# shield.net
KiCad netlist of a schematic drawn in Altium Designer
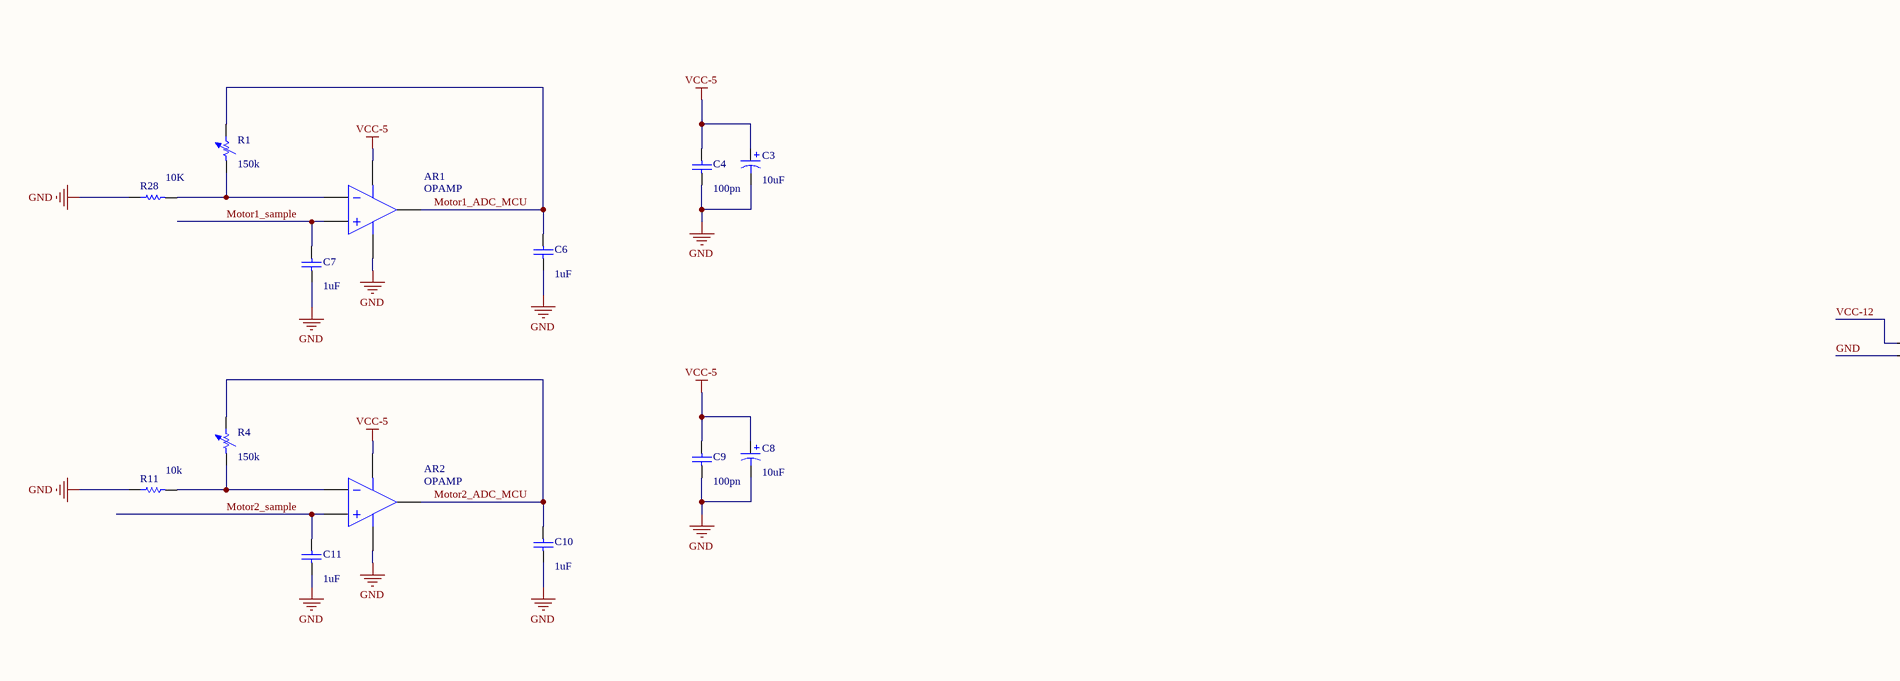
[diagram p0: shield.SchDoc, top left]
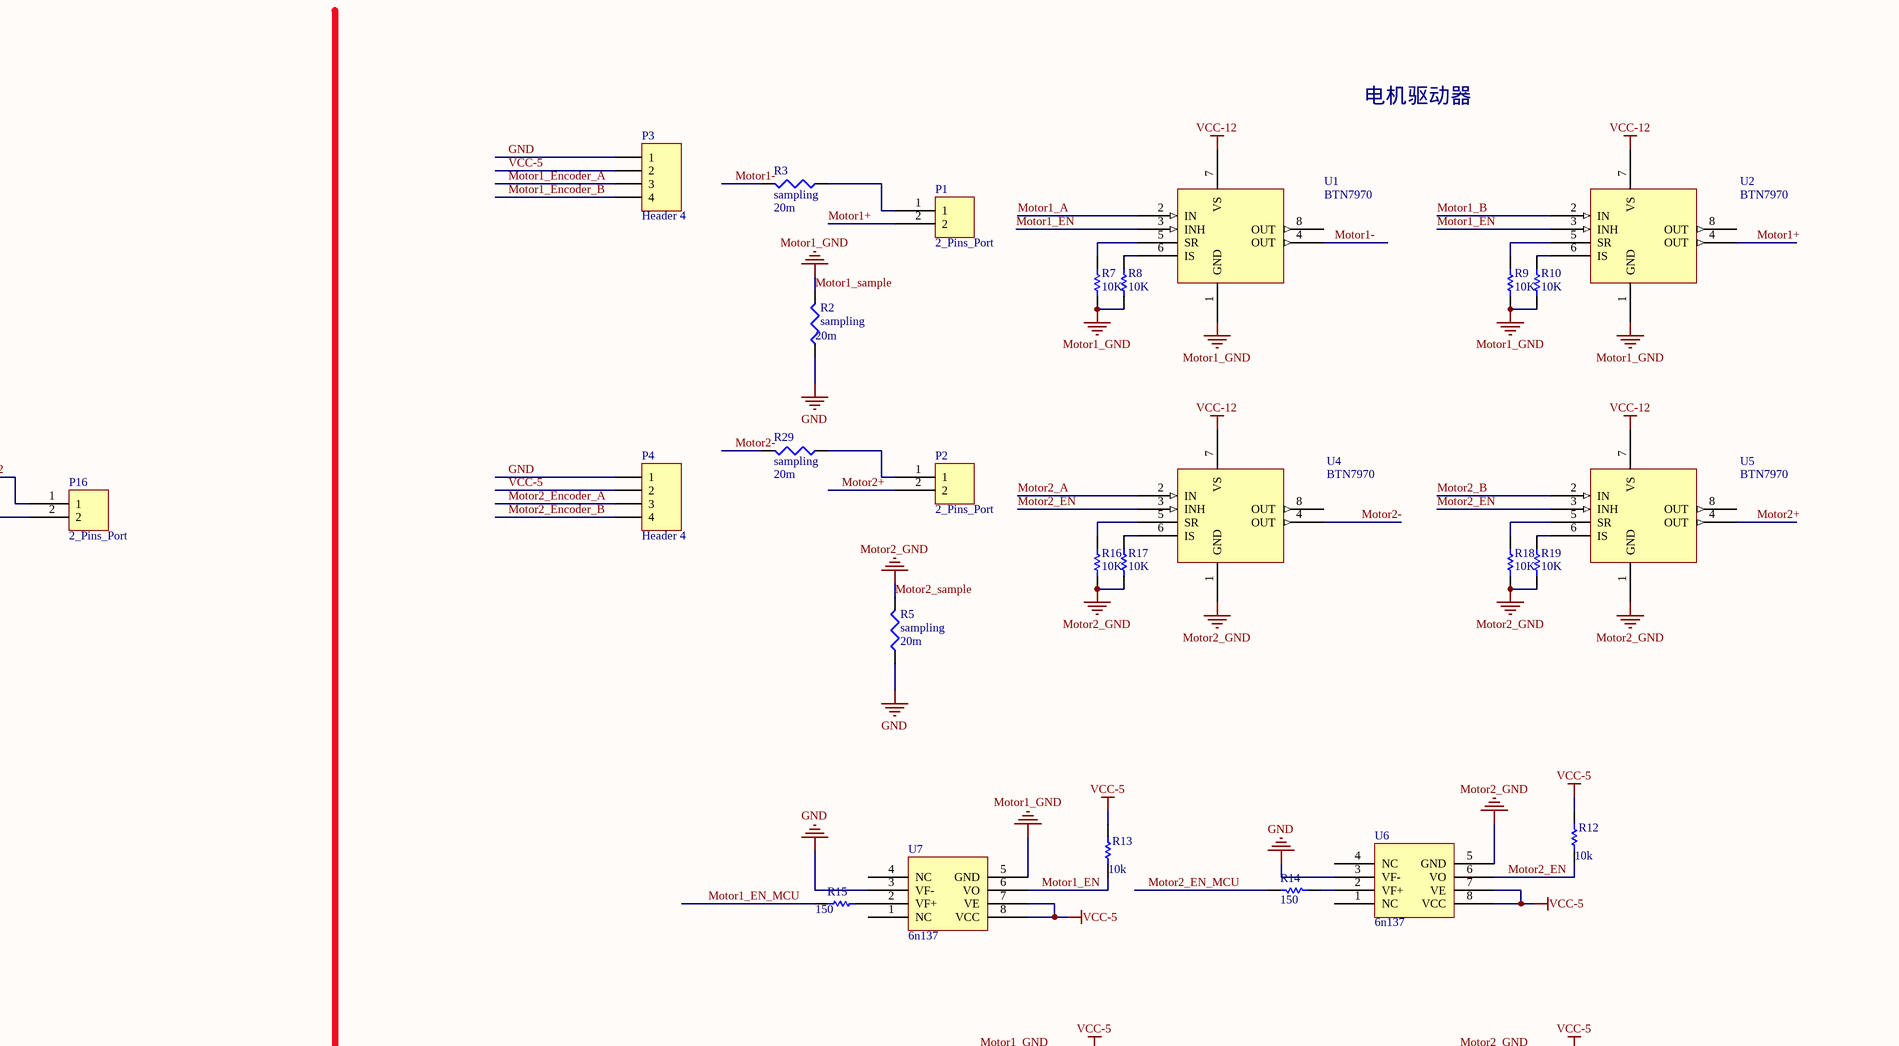
[diagram p1: shield.SchDoc, top right]
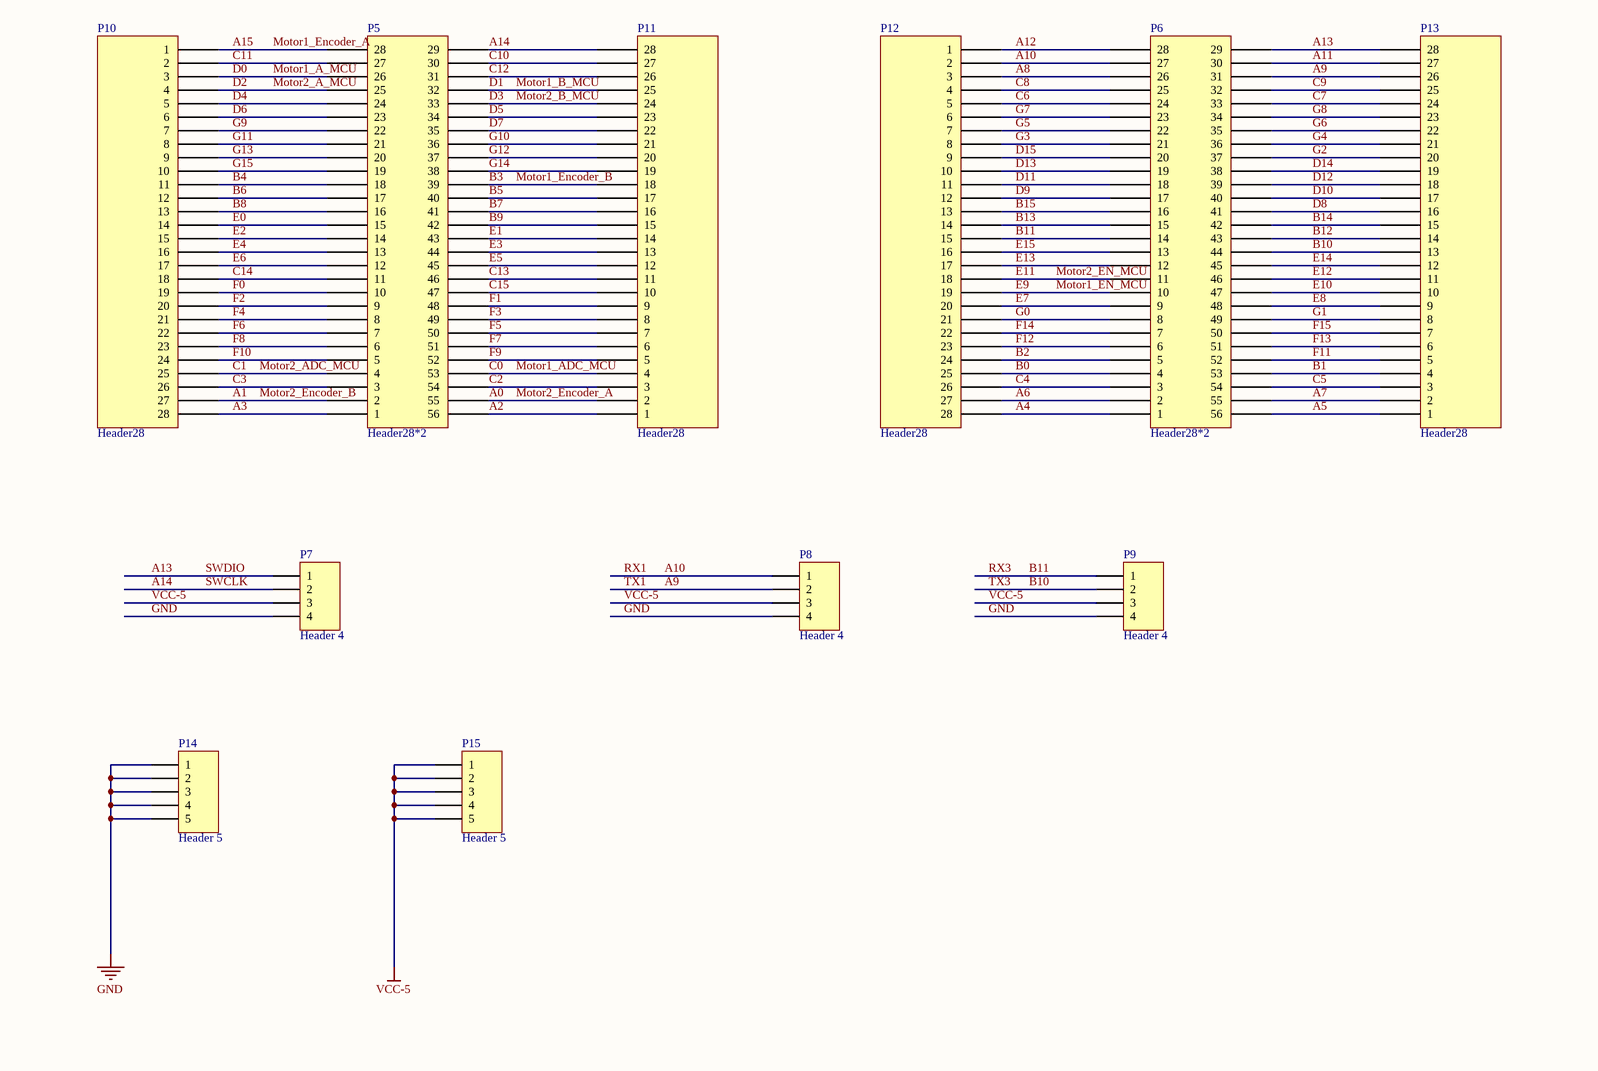
[diagram p2: shield.SchDoc, bottom left]
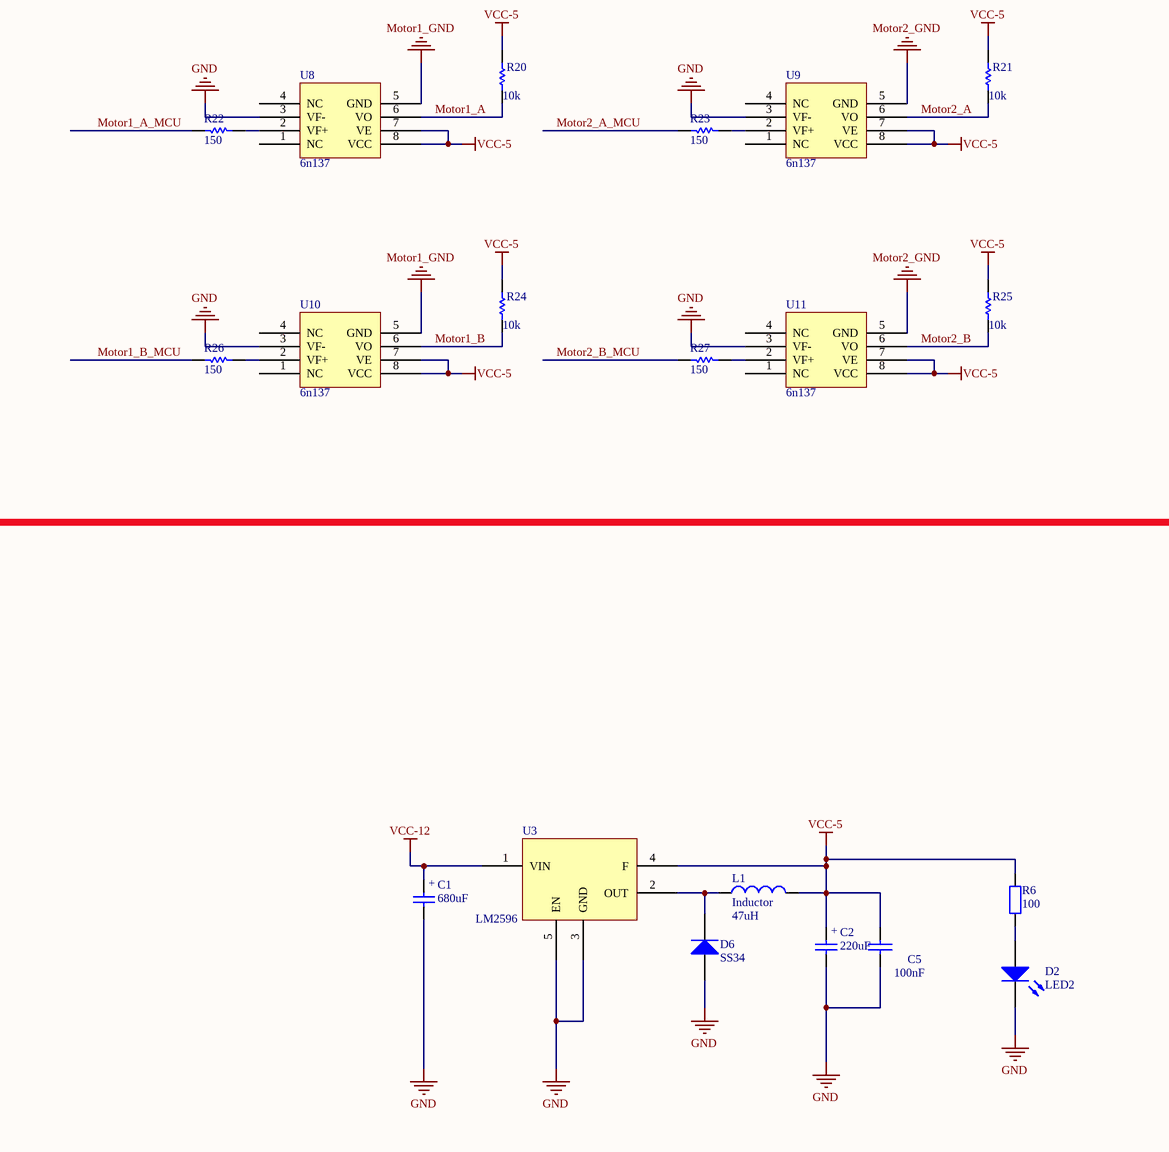
[diagram p3: shield.SchDoc, bottom right]

(export (version "E")
  (design (tool "Eeschema 10.0.6"))
  (components
    (comp (ref "AR1")
      (value "OPAMP")
      (footprint "LC-SO-8_3.9mm")
      (description "Operational Amplifier")
      (libsource (lib "SkyWorks2") (part "OPAMP"))
    )
    (comp (ref "AR2")
      (value "OPAMP")
      (footprint "LC-SO-8_3.9mm")
      (description "Operational Amplifier")
      (libsource (lib "SkyWorks2") (part "OPAMP"))
    )
    (comp (ref "C1")
      (value "680uF")
      (footprint "CAP-7343")
      (description "贴片极性电容")
      (fields (field (name "Comment") "Cap"))
      (libsource (lib "SkyWorks2") (part "Cap Pol S"))
    )
    (comp (ref "C2")
      (value "220uF")
      (footprint "CAP-7343")
      (description "贴片极性电容")
      (fields (field (name "Comment") "Cap"))
      (libsource (lib "SkyWorks2") (part "Cap Pol S"))
    )
    (comp (ref "C3")
      (value "10uF")
      (footprint "CAP-3528")
      (description "Polarized Capacitor (Radial)")
      (fields (field (name "Comment") "Cap Pol1") (field (name "PUBLISHER") "Altium Limited"))
      (libsource (lib "Miscellaneous Devices") (part "Cap Pol1"))
    )
    (comp (ref "C4")
      (value "100pn")
      (footprint "CAP-0603")
      (description "Capacitor")
      (fields (field (name "Comment") "Cap") (field (name "PUBLISHER") "Altium Limited"))
      (libsource (lib "Miscellaneous Devices") (part "Cap"))
    )
    (comp (ref "C5")
      (value "100nF")
      (footprint "CAP-0603")
      (description "贴片无极性电容")
      (fields (field (name "Comment") "cap smd"))
      (libsource (lib "SkyWorks2") (part "CAP"))
    )
    (comp (ref "C6")
      (value "1uF")
      (footprint "CAP-0603")
      (description "Capacitor")
      (fields (field (name "Comment") "Cap") (field (name "PUBLISHER") "Altium Limited"))
      (libsource (lib "Miscellaneous Devices") (part "Cap"))
    )
    (comp (ref "C7")
      (value "1uF")
      (footprint "CAP-0603")
      (description "Capacitor")
      (fields (field (name "Comment") "Cap") (field (name "PUBLISHER") "Altium Limited"))
      (libsource (lib "Miscellaneous Devices") (part "Cap"))
    )
    (comp (ref "C8")
      (value "10uF")
      (footprint "CAP-3528")
      (description "Polarized Capacitor (Radial)")
      (fields (field (name "Comment") "Cap Pol1") (field (name "PUBLISHER") "Altium Limited"))
      (libsource (lib "Miscellaneous Devices") (part "Cap Pol1"))
    )
    (comp (ref "C9")
      (value "100pn")
      (footprint "CAP-0603")
      (description "Capacitor")
      (fields (field (name "Comment") "Cap") (field (name "PUBLISHER") "Altium Limited"))
      (libsource (lib "Miscellaneous Devices") (part "Cap"))
    )
    (comp (ref "C10")
      (value "1uF")
      (footprint "CAP-0603")
      (description "Capacitor")
      (fields (field (name "Comment") "Cap") (field (name "PUBLISHER") "Altium Limited"))
      (libsource (lib "Miscellaneous Devices") (part "Cap"))
    )
    (comp (ref "C11")
      (value "1uF")
      (footprint "CAP-0603")
      (description "Capacitor")
      (fields (field (name "Comment") "Cap") (field (name "PUBLISHER") "Altium Limited"))
      (libsource (lib "Miscellaneous Devices") (part "Cap"))
    )
    (comp (ref "D2")
      (value "LED2")
      (footprint "D2012[0805]")
      (description "Typical RED, GREEN, YELLOW, AMBER GaAs LED")
      (fields (field (name "PUBLISHER") "Altium Limited"))
      (libsource (lib "SkyWorks2") (part "LED2"))
    )
    (comp (ref "D6")
      (value "SS34")
      (footprint "LC-SMB(DO-214AA)_S3")
      (description "3 Amp General Purpose Rectifier")
      (fields (field (name "PUBLISHER") "Altium Limited"))
      (libsource (lib "Miscellaneous Devices") (part "Diode 1N5400"))
    )
    (comp (ref "L1")
      (value "Inductor")
      (footprint "Inductor1207")
      (fields (field (name "ALTIUM_VALUE") "47uH") (field (name "PUBLISHER") "Altium Limited"))
      (libsource (lib "Miscellaneous Devices") (part "Inductor"))
    )
    (comp (ref "P1")
      (value "2_Pins_Port")
      (footprint "WJ2EDGV-5.08-2P")
      (libsource (lib "transhcan") (part "2_Pins_Port"))
    )
    (comp (ref "P2")
      (value "2_Pins_Port")
      (footprint "WJ2EDGV-5.08-2P")
      (libsource (lib "transhcan") (part "2_Pins_Port"))
    )
    (comp (ref "P3")
      (value "Header 4")
      (footprint "HDR1X4")
      (description "Header, 4-Pin")
      (fields (field (name "PUBLISHER") "Altium Limited"))
      (libsource (lib "Miscellaneous Connectors") (part "Header 4"))
    )
    (comp (ref "P4")
      (value "Header 4")
      (footprint "HDR1X4")
      (description "Header, 4-Pin")
      (fields (field (name "PUBLISHER") "Altium Limited"))
      (libsource (lib "Miscellaneous Connectors") (part "Header 4"))
    )
    (comp (ref "P5") (value "Header28*2") (footprint "HDR28*2") (libsource (lib "MLI") (part "header28*2")))
    (comp (ref "P6") (value "Header28*2") (footprint "HDR28*2") (libsource (lib "MLI") (part "header28*2")))
    (comp (ref "P7")
      (value "Header 4")
      (footprint "HDR1X4")
      (description "Header, 4-Pin")
      (fields (field (name "PUBLISHER") "Altium Limited"))
      (libsource (lib "Miscellaneous Connectors") (part "Header 4"))
    )
    (comp (ref "P8")
      (value "Header 4")
      (footprint "HDR1X4")
      (description "Header, 4-Pin")
      (fields (field (name "PUBLISHER") "Altium Limited"))
      (libsource (lib "Miscellaneous Connectors") (part "Header 4"))
    )
    (comp (ref "P9")
      (value "Header 4")
      (footprint "HDR1X4")
      (description "Header, 4-Pin")
      (fields (field (name "PUBLISHER") "Altium Limited"))
      (libsource (lib "Miscellaneous Connectors") (part "Header 4"))
    )
    (comp (ref "P10") (value "Header28") (footprint "HDR28") (libsource (lib "") (part "Header28_1")))
    (comp (ref "P11") (value "Header28") (footprint "HDR28") (libsource (lib "MLI") (part "Header28")))
    (comp (ref "P12") (value "Header28") (footprint "HDR28") (libsource (lib "") (part "Header28_1")))
    (comp (ref "P13") (value "Header28") (footprint "HDR28") (libsource (lib "MLI") (part "Header28")))
    (comp (ref "P14")
      (value "Header 5")
      (footprint "HDR1X5")
      (description "Header, 5-Pin")
      (fields (field (name "PUBLISHER") "Altium Limited"))
      (libsource (lib "Miscellaneous Connectors") (part "Header 5"))
    )
    (comp (ref "P15")
      (value "Header 5")
      (footprint "HDR1X5")
      (description "Header, 5-Pin")
      (fields (field (name "PUBLISHER") "Altium Limited"))
      (libsource (lib "Miscellaneous Connectors") (part "Header 5"))
    )
    (comp (ref "P16")
      (value "2_Pins_Port")
      (footprint "WJ2EDGV-5.08-2P")
      (libsource (lib "transhcan") (part "2_Pins_Port"))
    )
    (comp (ref "R1")
      (value "150k")
      (footprint "3266W")
      (description "Variable Resistor")
      (fields (field (name "Comment") "Res Adj1") (field (name "PUBLISHER") "Altium Limited"))
      (libsource (lib "Miscellaneous Devices") (part "Res Adj1"))
    )
    (comp (ref "R2")
      (value "sampling")
      (footprint "6332[2512]")
      (description "Resistor")
      (fields (field (name "ALTIUM_VALUE") "20m") (field (name "PUBLISHER") "Altium Limited"))
      (libsource (lib "Miscellaneous Devices") (part "Res3"))
    )
    (comp (ref "R3")
      (value "sampling")
      (footprint "6332[2512]")
      (description "Resistor")
      (fields (field (name "ALTIUM_VALUE") "20m") (field (name "PUBLISHER") "Altium Limited"))
      (libsource (lib "Miscellaneous Devices") (part "Res3"))
    )
    (comp (ref "R4")
      (value "150k")
      (footprint "3266W")
      (description "Variable Resistor")
      (fields (field (name "Comment") "Res Adj1") (field (name "PUBLISHER") "Altium Limited"))
      (libsource (lib "Miscellaneous Devices") (part "Res Adj1"))
    )
    (comp (ref "R5")
      (value "sampling")
      (footprint "6332[2512]")
      (description "Resistor")
      (fields (field (name "ALTIUM_VALUE") "20m") (field (name "PUBLISHER") "Altium Limited"))
      (libsource (lib "Miscellaneous Devices") (part "Res3"))
    )
    (comp (ref "R6")
      (value "100")
      (footprint "RES-0603")
      (fields (field (name "Comment") "RES1"))
      (libsource (lib "SkyWorks2") (part "RES1"))
    )
    (comp (ref "R7")
      (value "10K")
      (footprint "RES-0603")
      (description "Resistor")
      (libsource (lib "MCU") (part "res1"))
    )
    (comp (ref "R8")
      (value "10K")
      (footprint "RES-0603")
      (description "Resistor")
      (libsource (lib "MCU") (part "res1"))
    )
    (comp (ref "R9")
      (value "10K")
      (footprint "RES-0603")
      (description "Resistor")
      (libsource (lib "MCU") (part "res1"))
    )
    (comp (ref "R10")
      (value "10K")
      (footprint "RES-0603")
      (description "Resistor")
      (libsource (lib "MCU") (part "res1"))
    )
    (comp (ref "R11")
      (value "10k")
      (footprint "RES-0603")
      (description "Resistor")
      (fields (field (name "Comment") "Res1") (field (name "PUBLISHER") "Altium Limited"))
      (libsource (lib "Miscellaneous Devices") (part "Res1"))
    )
    (comp (ref "R12")
      (value "10k")
      (footprint "RES-0603")
      (description "Resistor")
      (fields (field (name "Comment") "Res1") (field (name "PUBLISHER") "Altium Limited"))
      (libsource (lib "Miscellaneous Devices") (part "Res1"))
    )
    (comp (ref "R13")
      (value "10k")
      (footprint "RES-0603")
      (description "Resistor")
      (fields (field (name "Comment") "Res1") (field (name "PUBLISHER") "Altium Limited"))
      (libsource (lib "Miscellaneous Devices") (part "Res1"))
    )
    (comp (ref "R14")
      (value "150")
      (footprint "RES-0603")
      (description "Resistor")
      (fields (field (name "Comment") "Res1") (field (name "PUBLISHER") "Altium Limited"))
      (libsource (lib "Miscellaneous Devices") (part "Res1"))
    )
    (comp (ref "R15")
      (value "150")
      (footprint "RES-0603")
      (description "Resistor")
      (fields (field (name "Comment") "Res1") (field (name "PUBLISHER") "Altium Limited"))
      (libsource (lib "Miscellaneous Devices") (part "Res1"))
    )
    (comp (ref "R16")
      (value "10K")
      (footprint "RES-0603")
      (description "Resistor")
      (libsource (lib "MCU") (part "res1"))
    )
    (comp (ref "R17")
      (value "10K")
      (footprint "RES-0603")
      (description "Resistor")
      (libsource (lib "MCU") (part "res1"))
    )
    (comp (ref "R18")
      (value "10K")
      (footprint "RES-0603")
      (description "Resistor")
      (libsource (lib "MCU") (part "res1"))
    )
    (comp (ref "R19")
      (value "10K")
      (footprint "RES-0603")
      (description "Resistor")
      (libsource (lib "MCU") (part "res1"))
    )
    (comp (ref "R20")
      (value "10k")
      (footprint "RES-0603")
      (description "Resistor")
      (fields (field (name "Comment") "Res1") (field (name "PUBLISHER") "Altium Limited"))
      (libsource (lib "Miscellaneous Devices") (part "Res1"))
    )
    (comp (ref "R21")
      (value "10k")
      (footprint "RES-0603")
      (description "Resistor")
      (fields (field (name "Comment") "Res1") (field (name "PUBLISHER") "Altium Limited"))
      (libsource (lib "Miscellaneous Devices") (part "Res1"))
    )
    (comp (ref "R22")
      (value "150")
      (footprint "RES-0603")
      (description "Resistor")
      (fields (field (name "Comment") "Res1") (field (name "PUBLISHER") "Altium Limited"))
      (libsource (lib "Miscellaneous Devices") (part "Res1"))
    )
    (comp (ref "R23")
      (value "150")
      (footprint "RES-0603")
      (description "Resistor")
      (fields (field (name "Comment") "Res1") (field (name "PUBLISHER") "Altium Limited"))
      (libsource (lib "Miscellaneous Devices") (part "Res1"))
    )
    (comp (ref "R24")
      (value "10k")
      (footprint "RES-0603")
      (description "Resistor")
      (fields (field (name "Comment") "Res1") (field (name "PUBLISHER") "Altium Limited"))
      (libsource (lib "Miscellaneous Devices") (part "Res1"))
    )
    (comp (ref "R25")
      (value "10k")
      (footprint "RES-0603")
      (description "Resistor")
      (fields (field (name "Comment") "Res1") (field (name "PUBLISHER") "Altium Limited"))
      (libsource (lib "Miscellaneous Devices") (part "Res1"))
    )
    (comp (ref "R26")
      (value "150")
      (footprint "RES-0603")
      (description "Resistor")
      (fields (field (name "Comment") "Res1") (field (name "PUBLISHER") "Altium Limited"))
      (libsource (lib "Miscellaneous Devices") (part "Res1"))
    )
    (comp (ref "R27")
      (value "150")
      (footprint "RES-0603")
      (description "Resistor")
      (fields (field (name "Comment") "Res1") (field (name "PUBLISHER") "Altium Limited"))
      (libsource (lib "Miscellaneous Devices") (part "Res1"))
    )
    (comp (ref "R28")
      (value "10K")
      (footprint "RES-0603")
      (description "Resistor")
      (fields (field (name "Comment") "Res1") (field (name "PUBLISHER") "Altium Limited"))
      (libsource (lib "Miscellaneous Devices") (part "Res1"))
    )
    (comp (ref "R29")
      (value "sampling")
      (footprint "6332[2512]")
      (description "Resistor")
      (fields (field (name "ALTIUM_VALUE") "20m") (field (name "PUBLISHER") "Altium Limited"))
      (libsource (lib "Miscellaneous Devices") (part "Res3"))
    )
    (comp (ref "U1") (value "BTN7970") (footprint "BTN7970") (libsource (lib "transhcan") (part "BTN7970")))
    (comp (ref "U2") (value "BTN7970") (footprint "BTN7970") (libsource (lib "transhcan") (part "BTN7970")))
    (comp (ref "U3") (value "LM2596") (footprint "LC-TO-263-5") (libsource (lib "MLI") (part "LM2596")))
    (comp (ref "U4") (value "BTN7970") (footprint "BTN7970") (libsource (lib "transhcan") (part "BTN7970")))
    (comp (ref "U5") (value "BTN7970") (footprint "BTN7970") (libsource (lib "transhcan") (part "BTN7970")))
    (comp (ref "U6") (value "6n137") (libsource (lib "MLI") (part "6n137")))
    (comp (ref "U7") (value "6n137") (libsource (lib "MLI") (part "6n137")))
    (comp (ref "U8") (value "6n137") (libsource (lib "MLI") (part "6n137")))
    (comp (ref "U9") (value "6n137") (libsource (lib "MLI") (part "6n137")))
    (comp (ref "U10") (value "6n137") (libsource (lib "MLI") (part "6n137")))
    (comp (ref "U11") (value "6n137") (libsource (lib "MLI") (part "6n137")))
  )
  (nets
    (net (code "1") (name "/A0") (class "Default")
      (node (ref "P11") (pin "2") (pinfunction "2_2") (pintype "passive"))
      (node (ref "P4") (pin "3") (pinfunction "3_3") (pintype "passive"))
      (node (ref "P5") (pin "55") (pinfunction "55_55") (pintype "passive"))
    )
    (net (code "2") (name "/A1") (class "Default")
      (node (ref "P10") (pin "27") (pinfunction "27_27") (pintype "passive"))
      (node (ref "P4") (pin "4") (pinfunction "4_4") (pintype "passive"))
      (node (ref "P5") (pin "2") (pinfunction "2_2") (pintype "passive"))
    )
    (net (code "3") (name "/A2") (class "Default")
      (node (ref "P11") (pin "1") (pinfunction "1_1") (pintype "passive"))
      (node (ref "P5") (pin "56") (pinfunction "56_56") (pintype "passive"))
    )
    (net (code "4") (name "/A3") (class "Default")
      (node (ref "P10") (pin "28") (pinfunction "28_28") (pintype "passive"))
      (node (ref "P5") (pin "1") (pinfunction "1_1") (pintype "passive"))
    )
    (net (code "5") (name "/A4") (class "Default")
      (node (ref "P12") (pin "28") (pinfunction "28_28") (pintype "passive"))
      (node (ref "P6") (pin "1") (pinfunction "1_1") (pintype "passive"))
    )
    (net (code "6") (name "/A5") (class "Default")
      (node (ref "P13") (pin "1") (pinfunction "1_1") (pintype "passive"))
      (node (ref "P6") (pin "56") (pinfunction "56_56") (pintype "passive"))
    )
    (net (code "7") (name "/A6") (class "Default")
      (node (ref "P12") (pin "27") (pinfunction "27_27") (pintype "passive"))
      (node (ref "P6") (pin "2") (pinfunction "2_2") (pintype "passive"))
    )
    (net (code "8") (name "/A7") (class "Default")
      (node (ref "P13") (pin "2") (pinfunction "2_2") (pintype "passive"))
      (node (ref "P6") (pin "55") (pinfunction "55_55") (pintype "passive"))
    )
    (net (code "9") (name "/A8") (class "Default")
      (node (ref "P12") (pin "3") (pinfunction "3_3") (pintype "passive"))
      (node (ref "P6") (pin "26") (pinfunction "26_26") (pintype "passive"))
    )
    (net (code "10") (name "/A9") (class "Default")
      (node (ref "P13") (pin "26") (pinfunction "26_26") (pintype "passive"))
      (node (ref "P6") (pin "31") (pinfunction "31_31") (pintype "passive"))
      (node (ref "P8") (pin "2") (pinfunction "2_2") (pintype "passive"))
    )
    (net (code "11") (name "/A10") (class "Default")
      (node (ref "P12") (pin "2") (pinfunction "2_2") (pintype "passive"))
      (node (ref "P6") (pin "27") (pinfunction "27_27") (pintype "passive"))
      (node (ref "P8") (pin "1") (pinfunction "1_1") (pintype "passive"))
    )
    (net (code "12") (name "/A11") (class "Default")
      (node (ref "P13") (pin "27") (pinfunction "27_27") (pintype "passive"))
      (node (ref "P6") (pin "30") (pinfunction "30_30") (pintype "passive"))
    )
    (net (code "13") (name "/A12") (class "Default")
      (node (ref "P12") (pin "1") (pinfunction "1_1") (pintype "passive"))
      (node (ref "P6") (pin "28") (pinfunction "28_28") (pintype "passive"))
    )
    (net (code "14") (name "/A13") (class "Default")
      (node (ref "P13") (pin "28") (pinfunction "28_28") (pintype "passive"))
      (node (ref "P6") (pin "29") (pinfunction "29_29") (pintype "passive"))
      (node (ref "P7") (pin "1") (pinfunction "1_1") (pintype "passive"))
    )
    (net (code "15") (name "/A14") (class "Default")
      (node (ref "P11") (pin "28") (pinfunction "28_28") (pintype "passive"))
      (node (ref "P5") (pin "29") (pinfunction "29_29") (pintype "passive"))
      (node (ref "P7") (pin "2") (pinfunction "2_2") (pintype "passive"))
    )
    (net (code "16") (name "/A15") (class "Default")
      (node (ref "P10") (pin "1") (pinfunction "1_1") (pintype "passive"))
      (node (ref "P3") (pin "3") (pinfunction "3_3") (pintype "passive"))
      (node (ref "P5") (pin "28") (pinfunction "28_28") (pintype "passive"))
    )
    (net (code "17") (name "/B0") (class "Default")
      (node (ref "P12") (pin "25") (pinfunction "25_25") (pintype "passive"))
      (node (ref "P6") (pin "4") (pinfunction "4_4") (pintype "passive"))
    )
    (net (code "18") (name "/B1") (class "Default")
      (node (ref "P13") (pin "4") (pinfunction "4_4") (pintype "passive"))
      (node (ref "P6") (pin "53") (pinfunction "53_53") (pintype "passive"))
    )
    (net (code "19") (name "/B2") (class "Default")
      (node (ref "P12") (pin "24") (pinfunction "24_24") (pintype "passive"))
      (node (ref "P6") (pin "5") (pinfunction "5_5") (pintype "passive"))
    )
    (net (code "20") (name "/B3") (class "Default")
      (node (ref "P11") (pin "18") (pinfunction "18_18") (pintype "passive"))
      (node (ref "P3") (pin "4") (pinfunction "4_4") (pintype "passive"))
      (node (ref "P5") (pin "39") (pinfunction "39_39") (pintype "passive"))
    )
    (net (code "21") (name "/B4") (class "Default")
      (node (ref "P10") (pin "11") (pinfunction "11_11") (pintype "passive"))
      (node (ref "P5") (pin "18") (pinfunction "18_18") (pintype "passive"))
    )
    (net (code "22") (name "/B5") (class "Default")
      (node (ref "P11") (pin "17") (pinfunction "17_17") (pintype "passive"))
      (node (ref "P5") (pin "40") (pinfunction "40_40") (pintype "passive"))
    )
    (net (code "23") (name "/B6") (class "Default")
      (node (ref "P10") (pin "12") (pinfunction "12_12") (pintype "passive"))
      (node (ref "P5") (pin "17") (pinfunction "17_17") (pintype "passive"))
    )
    (net (code "24") (name "/B7") (class "Default")
      (node (ref "P11") (pin "16") (pinfunction "16_16") (pintype "passive"))
      (node (ref "P5") (pin "41") (pinfunction "41_41") (pintype "passive"))
    )
    (net (code "25") (name "/B8") (class "Default")
      (node (ref "P10") (pin "13") (pinfunction "13_13") (pintype "passive"))
      (node (ref "P5") (pin "16") (pinfunction "16_16") (pintype "passive"))
    )
    (net (code "26") (name "/B9") (class "Default")
      (node (ref "P11") (pin "15") (pinfunction "15_15") (pintype "passive"))
      (node (ref "P5") (pin "42") (pinfunction "42_42") (pintype "passive"))
    )
    (net (code "27") (name "/B10") (class "Default")
      (node (ref "P13") (pin "13") (pinfunction "13_13") (pintype "passive"))
      (node (ref "P6") (pin "44") (pinfunction "44_44") (pintype "passive"))
      (node (ref "P9") (pin "2") (pinfunction "2_2") (pintype "passive"))
    )
    (net (code "28") (name "/B11") (class "Default")
      (node (ref "P12") (pin "15") (pinfunction "15_15") (pintype "passive"))
      (node (ref "P6") (pin "14") (pinfunction "14_14") (pintype "passive"))
      (node (ref "P9") (pin "1") (pinfunction "1_1") (pintype "passive"))
    )
    (net (code "29") (name "/B12") (class "Default")
      (node (ref "P13") (pin "14") (pinfunction "14_14") (pintype "passive"))
      (node (ref "P6") (pin "43") (pinfunction "43_43") (pintype "passive"))
    )
    (net (code "30") (name "/B13") (class "Default")
      (node (ref "P12") (pin "14") (pinfunction "14_14") (pintype "passive"))
      (node (ref "P6") (pin "15") (pinfunction "15_15") (pintype "passive"))
    )
    (net (code "31") (name "/B14") (class "Default")
      (node (ref "P13") (pin "15") (pinfunction "15_15") (pintype "passive"))
      (node (ref "P6") (pin "42") (pinfunction "42_42") (pintype "passive"))
    )
    (net (code "32") (name "/B15") (class "Default")
      (node (ref "P12") (pin "13") (pinfunction "13_13") (pintype "passive"))
      (node (ref "P6") (pin "16") (pinfunction "16_16") (pintype "passive"))
    )
    (net (code "33") (name "/C0") (class "Default")
      (node (ref "AR1") (pin "3") (pinfunction "OUT_3") (pintype "passive"))
      (node (ref "C6") (pin "2") (pinfunction "2_2") (pintype "passive"))
      (node (ref "P11") (pin "4") (pinfunction "4_4") (pintype "passive"))
      (node (ref "P5") (pin "53") (pinfunction "53_53") (pintype "passive"))
      (node (ref "R1") (pin "2") (pinfunction "2_2") (pintype "passive"))
    )
    (net (code "34") (name "/C1") (class "Default")
      (node (ref "AR2") (pin "3") (pinfunction "OUT_3") (pintype "passive"))
      (node (ref "C10") (pin "2") (pinfunction "2_2") (pintype "passive"))
      (node (ref "P10") (pin "25") (pinfunction "25_25") (pintype "passive"))
      (node (ref "P5") (pin "4") (pinfunction "4_4") (pintype "passive"))
      (node (ref "R4") (pin "2") (pinfunction "2_2") (pintype "passive"))
    )
    (net (code "35") (name "/C2") (class "Default")
      (node (ref "P11") (pin "3") (pinfunction "3_3") (pintype "passive"))
      (node (ref "P5") (pin "54") (pinfunction "54_54") (pintype "passive"))
    )
    (net (code "36") (name "/C3") (class "Default")
      (node (ref "P10") (pin "26") (pinfunction "26_26") (pintype "passive"))
      (node (ref "P5") (pin "3") (pinfunction "3_3") (pintype "passive"))
    )
    (net (code "37") (name "/C4") (class "Default")
      (node (ref "P12") (pin "26") (pinfunction "26_26") (pintype "passive"))
      (node (ref "P6") (pin "3") (pinfunction "3_3") (pintype "passive"))
    )
    (net (code "38") (name "/C5") (class "Default")
      (node (ref "P13") (pin "3") (pinfunction "3_3") (pintype "passive"))
      (node (ref "P6") (pin "54") (pinfunction "54_54") (pintype "passive"))
    )
    (net (code "39") (name "/C6") (class "Default")
      (node (ref "P12") (pin "5") (pinfunction "5_5") (pintype "passive"))
      (node (ref "P6") (pin "24") (pinfunction "24_24") (pintype "passive"))
    )
    (net (code "40") (name "/C7") (class "Default")
      (node (ref "P13") (pin "24") (pinfunction "24_24") (pintype "passive"))
      (node (ref "P6") (pin "33") (pinfunction "33_33") (pintype "passive"))
    )
    (net (code "41") (name "/C8") (class "Default")
      (node (ref "P12") (pin "4") (pinfunction "4_4") (pintype "passive"))
      (node (ref "P6") (pin "25") (pinfunction "25_25") (pintype "passive"))
    )
    (net (code "42") (name "/C9") (class "Default")
      (node (ref "P13") (pin "25") (pinfunction "25_25") (pintype "passive"))
      (node (ref "P6") (pin "32") (pinfunction "32_32") (pintype "passive"))
    )
    (net (code "43") (name "/C10") (class "Default")
      (node (ref "P11") (pin "27") (pinfunction "27_27") (pintype "passive"))
      (node (ref "P5") (pin "30") (pinfunction "30_30") (pintype "passive"))
    )
    (net (code "44") (name "/C11") (class "Default")
      (node (ref "P10") (pin "2") (pinfunction "2_2") (pintype "passive"))
      (node (ref "P5") (pin "27") (pinfunction "27_27") (pintype "passive"))
    )
    (net (code "45") (name "/C12") (class "Default")
      (node (ref "P11") (pin "26") (pinfunction "26_26") (pintype "passive"))
      (node (ref "P5") (pin "31") (pinfunction "31_31") (pintype "passive"))
    )
    (net (code "46") (name "/C13") (class "Default")
      (node (ref "P11") (pin "11") (pinfunction "11_11") (pintype "passive"))
      (node (ref "P5") (pin "46") (pinfunction "46_46") (pintype "passive"))
    )
    (net (code "47") (name "/C14") (class "Default")
      (node (ref "P10") (pin "18") (pinfunction "18_18") (pintype "passive"))
      (node (ref "P5") (pin "11") (pinfunction "11_11") (pintype "passive"))
    )
    (net (code "48") (name "/C15") (class "Default")
      (node (ref "P11") (pin "10") (pinfunction "10_10") (pintype "passive"))
      (node (ref "P5") (pin "47") (pinfunction "47_47") (pintype "passive"))
    )
    (net (code "49") (name "/D0") (class "Default")
      (node (ref "P10") (pin "3") (pinfunction "3_3") (pintype "passive"))
      (node (ref "P5") (pin "26") (pinfunction "26_26") (pintype "passive"))
      (node (ref "R22") (pin "2") (pinfunction "2_2") (pintype "passive"))
    )
    (net (code "50") (name "/D1") (class "Default")
      (node (ref "P11") (pin "25") (pinfunction "25_25") (pintype "passive"))
      (node (ref "P5") (pin "32") (pinfunction "32_32") (pintype "passive"))
      (node (ref "R26") (pin "2") (pinfunction "2_2") (pintype "passive"))
    )
    (net (code "51") (name "/D2") (class "Default")
      (node (ref "P10") (pin "4") (pinfunction "4_4") (pintype "passive"))
      (node (ref "P5") (pin "25") (pinfunction "25_25") (pintype "passive"))
      (node (ref "R23") (pin "2") (pinfunction "2_2") (pintype "passive"))
    )
    (net (code "52") (name "/D3") (class "Default")
      (node (ref "P11") (pin "24") (pinfunction "24_24") (pintype "passive"))
      (node (ref "P5") (pin "33") (pinfunction "33_33") (pintype "passive"))
      (node (ref "R27") (pin "2") (pinfunction "2_2") (pintype "passive"))
    )
    (net (code "53") (name "/D4") (class "Default")
      (node (ref "P10") (pin "5") (pinfunction "5_5") (pintype "passive"))
      (node (ref "P5") (pin "24") (pinfunction "24_24") (pintype "passive"))
    )
    (net (code "54") (name "/D5") (class "Default")
      (node (ref "P11") (pin "23") (pinfunction "23_23") (pintype "passive"))
      (node (ref "P5") (pin "34") (pinfunction "34_34") (pintype "passive"))
    )
    (net (code "55") (name "/D6") (class "Default")
      (node (ref "P10") (pin "6") (pinfunction "6_6") (pintype "passive"))
      (node (ref "P5") (pin "23") (pinfunction "23_23") (pintype "passive"))
    )
    (net (code "56") (name "/D7") (class "Default")
      (node (ref "P11") (pin "22") (pinfunction "22_22") (pintype "passive"))
      (node (ref "P5") (pin "35") (pinfunction "35_35") (pintype "passive"))
    )
    (net (code "57") (name "/D8") (class "Default")
      (node (ref "P13") (pin "16") (pinfunction "16_16") (pintype "passive"))
      (node (ref "P6") (pin "41") (pinfunction "41_41") (pintype "passive"))
    )
    (net (code "58") (name "/D9") (class "Default")
      (node (ref "P12") (pin "12") (pinfunction "12_12") (pintype "passive"))
      (node (ref "P6") (pin "17") (pinfunction "17_17") (pintype "passive"))
    )
    (net (code "59") (name "/D10") (class "Default")
      (node (ref "P13") (pin "17") (pinfunction "17_17") (pintype "passive"))
      (node (ref "P6") (pin "40") (pinfunction "40_40") (pintype "passive"))
    )
    (net (code "60") (name "/D11") (class "Default")
      (node (ref "P12") (pin "11") (pinfunction "11_11") (pintype "passive"))
      (node (ref "P6") (pin "18") (pinfunction "18_18") (pintype "passive"))
    )
    (net (code "61") (name "/D12") (class "Default")
      (node (ref "P13") (pin "18") (pinfunction "18_18") (pintype "passive"))
      (node (ref "P6") (pin "39") (pinfunction "39_39") (pintype "passive"))
    )
    (net (code "62") (name "/D13") (class "Default")
      (node (ref "P12") (pin "10") (pinfunction "10_10") (pintype "passive"))
      (node (ref "P6") (pin "19") (pinfunction "19_19") (pintype "passive"))
    )
    (net (code "63") (name "/D14") (class "Default")
      (node (ref "P13") (pin "19") (pinfunction "19_19") (pintype "passive"))
      (node (ref "P6") (pin "38") (pinfunction "38_38") (pintype "passive"))
    )
    (net (code "64") (name "/D15") (class "Default")
      (node (ref "P12") (pin "9") (pinfunction "9_9") (pintype "passive"))
      (node (ref "P6") (pin "20") (pinfunction "20_20") (pintype "passive"))
    )
    (net (code "65") (name "/E0") (class "Default")
      (node (ref "P10") (pin "14") (pinfunction "14_14") (pintype "passive"))
      (node (ref "P5") (pin "15") (pinfunction "15_15") (pintype "passive"))
    )
    (net (code "66") (name "/E1") (class "Default")
      (node (ref "P11") (pin "14") (pinfunction "14_14") (pintype "passive"))
      (node (ref "P5") (pin "43") (pinfunction "43_43") (pintype "passive"))
    )
    (net (code "67") (name "/E2") (class "Default")
      (node (ref "P10") (pin "15") (pinfunction "15_15") (pintype "passive"))
      (node (ref "P5") (pin "14") (pinfunction "14_14") (pintype "passive"))
    )
    (net (code "68") (name "/E3") (class "Default")
      (node (ref "P11") (pin "13") (pinfunction "13_13") (pintype "passive"))
      (node (ref "P5") (pin "44") (pinfunction "44_44") (pintype "passive"))
    )
    (net (code "69") (name "/E4") (class "Default")
      (node (ref "P10") (pin "16") (pinfunction "16_16") (pintype "passive"))
      (node (ref "P5") (pin "13") (pinfunction "13_13") (pintype "passive"))
    )
    (net (code "70") (name "/E5") (class "Default")
      (node (ref "P11") (pin "12") (pinfunction "12_12") (pintype "passive"))
      (node (ref "P5") (pin "45") (pinfunction "45_45") (pintype "passive"))
    )
    (net (code "71") (name "/E6") (class "Default")
      (node (ref "P10") (pin "17") (pinfunction "17_17") (pintype "passive"))
      (node (ref "P5") (pin "12") (pinfunction "12_12") (pintype "passive"))
    )
    (net (code "72") (name "/E7") (class "Default")
      (node (ref "P12") (pin "20") (pinfunction "20_20") (pintype "passive"))
      (node (ref "P6") (pin "9") (pinfunction "9_9") (pintype "passive"))
    )
    (net (code "73") (name "/E8") (class "Default")
      (node (ref "P13") (pin "9") (pinfunction "9_9") (pintype "passive"))
      (node (ref "P6") (pin "48") (pinfunction "48_48") (pintype "passive"))
    )
    (net (code "74") (name "/E9") (class "Default")
      (node (ref "P12") (pin "19") (pinfunction "19_19") (pintype "passive"))
      (node (ref "P6") (pin "10") (pinfunction "10_10") (pintype "passive"))
      (node (ref "R15") (pin "2") (pinfunction "2_2") (pintype "passive"))
    )
    (net (code "75") (name "/E10") (class "Default")
      (node (ref "P13") (pin "10") (pinfunction "10_10") (pintype "passive"))
      (node (ref "P6") (pin "47") (pinfunction "47_47") (pintype "passive"))
    )
    (net (code "76") (name "/E11") (class "Default")
      (node (ref "P12") (pin "18") (pinfunction "18_18") (pintype "passive"))
      (node (ref "P6") (pin "11") (pinfunction "11_11") (pintype "passive"))
      (node (ref "R14") (pin "2") (pinfunction "2_2") (pintype "passive"))
    )
    (net (code "77") (name "/E12") (class "Default")
      (node (ref "P13") (pin "11") (pinfunction "11_11") (pintype "passive"))
      (node (ref "P6") (pin "46") (pinfunction "46_46") (pintype "passive"))
    )
    (net (code "78") (name "/E13") (class "Default")
      (node (ref "P12") (pin "17") (pinfunction "17_17") (pintype "passive"))
      (node (ref "P6") (pin "12") (pinfunction "12_12") (pintype "passive"))
    )
    (net (code "79") (name "/E14") (class "Default")
      (node (ref "P13") (pin "12") (pinfunction "12_12") (pintype "passive"))
      (node (ref "P6") (pin "45") (pinfunction "45_45") (pintype "passive"))
    )
    (net (code "80") (name "/E15") (class "Default")
      (node (ref "P12") (pin "16") (pinfunction "16_16") (pintype "passive"))
      (node (ref "P6") (pin "13") (pinfunction "13_13") (pintype "passive"))
    )
    (net (code "81") (name "/F0") (class "Default")
      (node (ref "P10") (pin "19") (pinfunction "19_19") (pintype "passive"))
      (node (ref "P5") (pin "10") (pinfunction "10_10") (pintype "passive"))
    )
    (net (code "82") (name "/F1") (class "Default")
      (node (ref "P11") (pin "9") (pinfunction "9_9") (pintype "passive"))
      (node (ref "P5") (pin "48") (pinfunction "48_48") (pintype "passive"))
    )
    (net (code "83") (name "/F2") (class "Default")
      (node (ref "P10") (pin "20") (pinfunction "20_20") (pintype "passive"))
      (node (ref "P5") (pin "9") (pinfunction "9_9") (pintype "passive"))
    )
    (net (code "84") (name "/F3") (class "Default")
      (node (ref "P11") (pin "8") (pinfunction "8_8") (pintype "passive"))
      (node (ref "P5") (pin "49") (pinfunction "49_49") (pintype "passive"))
    )
    (net (code "85") (name "/F4") (class "Default")
      (node (ref "P10") (pin "21") (pinfunction "21_21") (pintype "passive"))
      (node (ref "P5") (pin "8") (pinfunction "8_8") (pintype "passive"))
    )
    (net (code "86") (name "/F5") (class "Default")
      (node (ref "P11") (pin "7") (pinfunction "7_7") (pintype "passive"))
      (node (ref "P5") (pin "50") (pinfunction "50_50") (pintype "passive"))
    )
    (net (code "87") (name "/F6") (class "Default")
      (node (ref "P10") (pin "22") (pinfunction "22_22") (pintype "passive"))
      (node (ref "P5") (pin "7") (pinfunction "7_7") (pintype "passive"))
    )
    (net (code "88") (name "/F7") (class "Default")
      (node (ref "P11") (pin "6") (pinfunction "6_6") (pintype "passive"))
      (node (ref "P5") (pin "51") (pinfunction "51_51") (pintype "passive"))
    )
    (net (code "89") (name "/F8") (class "Default")
      (node (ref "P10") (pin "23") (pinfunction "23_23") (pintype "passive"))
      (node (ref "P5") (pin "6") (pinfunction "6_6") (pintype "passive"))
    )
    (net (code "90") (name "/F9") (class "Default")
      (node (ref "P11") (pin "5") (pinfunction "5_5") (pintype "passive"))
      (node (ref "P5") (pin "52") (pinfunction "52_52") (pintype "passive"))
    )
    (net (code "91") (name "/F10") (class "Default")
      (node (ref "P10") (pin "24") (pinfunction "24_24") (pintype "passive"))
      (node (ref "P5") (pin "5") (pinfunction "5_5") (pintype "passive"))
    )
    (net (code "92") (name "/F11") (class "Default")
      (node (ref "P13") (pin "5") (pinfunction "5_5") (pintype "passive"))
      (node (ref "P6") (pin "52") (pinfunction "52_52") (pintype "passive"))
    )
    (net (code "93") (name "/F12") (class "Default")
      (node (ref "P12") (pin "23") (pinfunction "23_23") (pintype "passive"))
      (node (ref "P6") (pin "6") (pinfunction "6_6") (pintype "passive"))
    )
    (net (code "94") (name "/F13") (class "Default")
      (node (ref "P13") (pin "6") (pinfunction "6_6") (pintype "passive"))
      (node (ref "P6") (pin "51") (pinfunction "51_51") (pintype "passive"))
    )
    (net (code "95") (name "/F14") (class "Default")
      (node (ref "P12") (pin "22") (pinfunction "22_22") (pintype "passive"))
      (node (ref "P6") (pin "7") (pinfunction "7_7") (pintype "passive"))
    )
    (net (code "96") (name "/F15") (class "Default")
      (node (ref "P13") (pin "7") (pinfunction "7_7") (pintype "passive"))
      (node (ref "P6") (pin "50") (pinfunction "50_50") (pintype "passive"))
    )
    (net (code "97") (name "/G0") (class "Default")
      (node (ref "P12") (pin "21") (pinfunction "21_21") (pintype "passive"))
      (node (ref "P6") (pin "8") (pinfunction "8_8") (pintype "passive"))
    )
    (net (code "98") (name "/G1") (class "Default")
      (node (ref "P13") (pin "8") (pinfunction "8_8") (pintype "passive"))
      (node (ref "P6") (pin "49") (pinfunction "49_49") (pintype "passive"))
    )
    (net (code "99") (name "/G2") (class "Default")
      (node (ref "P13") (pin "20") (pinfunction "20_20") (pintype "passive"))
      (node (ref "P6") (pin "37") (pinfunction "37_37") (pintype "passive"))
    )
    (net (code "100") (name "/G3") (class "Default")
      (node (ref "P12") (pin "8") (pinfunction "8_8") (pintype "passive"))
      (node (ref "P6") (pin "21") (pinfunction "21_21") (pintype "passive"))
    )
    (net (code "101") (name "/G4") (class "Default")
      (node (ref "P13") (pin "21") (pinfunction "21_21") (pintype "passive"))
      (node (ref "P6") (pin "36") (pinfunction "36_36") (pintype "passive"))
    )
    (net (code "102") (name "/G5") (class "Default")
      (node (ref "P12") (pin "7") (pinfunction "7_7") (pintype "passive"))
      (node (ref "P6") (pin "22") (pinfunction "22_22") (pintype "passive"))
    )
    (net (code "103") (name "/G6") (class "Default")
      (node (ref "P13") (pin "22") (pinfunction "22_22") (pintype "passive"))
      (node (ref "P6") (pin "35") (pinfunction "35_35") (pintype "passive"))
    )
    (net (code "104") (name "/G7") (class "Default")
      (node (ref "P12") (pin "6") (pinfunction "6_6") (pintype "passive"))
      (node (ref "P6") (pin "23") (pinfunction "23_23") (pintype "passive"))
    )
    (net (code "105") (name "/G8") (class "Default")
      (node (ref "P13") (pin "23") (pinfunction "23_23") (pintype "passive"))
      (node (ref "P6") (pin "34") (pinfunction "34_34") (pintype "passive"))
    )
    (net (code "106") (name "/G9") (class "Default")
      (node (ref "P10") (pin "7") (pinfunction "7_7") (pintype "passive"))
      (node (ref "P5") (pin "22") (pinfunction "22_22") (pintype "passive"))
    )
    (net (code "107") (name "/G10") (class "Default")
      (node (ref "P11") (pin "21") (pinfunction "21_21") (pintype "passive"))
      (node (ref "P5") (pin "36") (pinfunction "36_36") (pintype "passive"))
    )
    (net (code "108") (name "/G11") (class "Default")
      (node (ref "P10") (pin "8") (pinfunction "8_8") (pintype "passive"))
      (node (ref "P5") (pin "21") (pinfunction "21_21") (pintype "passive"))
    )
    (net (code "109") (name "/G12") (class "Default")
      (node (ref "P11") (pin "20") (pinfunction "20_20") (pintype "passive"))
      (node (ref "P5") (pin "37") (pinfunction "37_37") (pintype "passive"))
    )
    (net (code "110") (name "/G13") (class "Default")
      (node (ref "P10") (pin "9") (pinfunction "9_9") (pintype "passive"))
      (node (ref "P5") (pin "20") (pinfunction "20_20") (pintype "passive"))
    )
    (net (code "111") (name "/G14") (class "Default")
      (node (ref "P11") (pin "19") (pinfunction "19_19") (pintype "passive"))
      (node (ref "P5") (pin "38") (pinfunction "38_38") (pintype "passive"))
    )
    (net (code "112") (name "/G15") (class "Default")
      (node (ref "P10") (pin "10") (pinfunction "10_10") (pintype "passive"))
      (node (ref "P5") (pin "19") (pinfunction "19_19") (pintype "passive"))
    )
    (net (code "113") (name "/Motor1+") (class "Default")
      (node (ref "P1") (pin "2") (pinfunction "2_2") (pintype "passive"))
      (node (ref "U2") (pin "4") (pinfunction "OUT_4") (pintype "output"))
    )
    (net (code "114") (name "/Motor1-") (class "Default")
      (node (ref "R3") (pin "2") (pinfunction "2_2") (pintype "passive"))
      (node (ref "U1") (pin "4") (pinfunction "OUT_4") (pintype "output"))
    )
    (net (code "115") (name "/Motor1_A") (class "Default")
      (node (ref "R20") (pin "1") (pinfunction "1_1") (pintype "passive"))
      (node (ref "U1") (pin "2") (pinfunction "IN_2") (pintype "input"))
      (node (ref "U8") (pin "6") (pinfunction "VO_6") (pintype "passive"))
    )
    (net (code "116") (name "/Motor1_B") (class "Default")
      (node (ref "R24") (pin "1") (pinfunction "1_1") (pintype "passive"))
      (node (ref "U10") (pin "6") (pinfunction "VO_6") (pintype "passive"))
      (node (ref "U2") (pin "2") (pinfunction "IN_2") (pintype "input"))
    )
    (net (code "117") (name "/Motor1_EN") (class "Default")
      (node (ref "R13") (pin "1") (pinfunction "1_1") (pintype "passive"))
      (node (ref "U1") (pin "3") (pinfunction "INH_3") (pintype "input"))
      (node (ref "U2") (pin "3") (pinfunction "INH_3") (pintype "input"))
      (node (ref "U7") (pin "6") (pinfunction "VO_6") (pintype "passive"))
    )
    (net (code "118") (name "/Motor2+") (class "Default")
      (node (ref "P2") (pin "2") (pinfunction "2_2") (pintype "passive"))
      (node (ref "U5") (pin "4") (pinfunction "OUT_4") (pintype "output"))
    )
    (net (code "119") (name "/Motor2-") (class "Default")
      (node (ref "R29") (pin "2") (pinfunction "2_2") (pintype "passive"))
      (node (ref "U4") (pin "4") (pinfunction "OUT_4") (pintype "output"))
    )
    (net (code "120") (name "/Motor2_A") (class "Default")
      (node (ref "R21") (pin "1") (pinfunction "1_1") (pintype "passive"))
      (node (ref "U4") (pin "2") (pinfunction "IN_2") (pintype "input"))
      (node (ref "U9") (pin "6") (pinfunction "VO_6") (pintype "passive"))
    )
    (net (code "121") (name "/Motor2_B") (class "Default")
      (node (ref "R25") (pin "1") (pinfunction "1_1") (pintype "passive"))
      (node (ref "U11") (pin "6") (pinfunction "VO_6") (pintype "passive"))
      (node (ref "U5") (pin "2") (pinfunction "IN_2") (pintype "input"))
    )
    (net (code "122") (name "/Motor2_EN") (class "Default")
      (node (ref "R12") (pin "1") (pinfunction "1_1") (pintype "passive"))
      (node (ref "U4") (pin "3") (pinfunction "INH_3") (pintype "input"))
      (node (ref "U5") (pin "3") (pinfunction "INH_3") (pintype "input"))
      (node (ref "U6") (pin "6") (pinfunction "VO_6") (pintype "passive"))
    )
    (net (code "123") (name "GND") (class "Default")
      (node (ref "AR1") (pin "5") (pinfunction "V-_5") (pintype "passive"))
      (node (ref "AR2") (pin "5") (pinfunction "V-_5") (pintype "passive"))
      (node (ref "C1") (pin "2") (pinfunction "-_2") (pintype "passive"))
      (node (ref "C10") (pin "1") (pinfunction "1_1") (pintype "passive"))
      (node (ref "C11") (pin "1") (pinfunction "1_1") (pintype "passive"))
      (node (ref "C2") (pin "2") (pinfunction "-_2") (pintype "passive"))
      (node (ref "C3") (pin "2") (pinfunction "2_2") (pintype "passive"))
      (node (ref "C4") (pin "1") (pinfunction "1_1") (pintype "passive"))
      (node (ref "C5") (pin "2") (pinfunction "2_2") (pintype "passive"))
      (node (ref "C6") (pin "1") (pinfunction "1_1") (pintype "passive"))
      (node (ref "C7") (pin "1") (pinfunction "1_1") (pintype "passive"))
      (node (ref "C8") (pin "2") (pinfunction "2_2") (pintype "passive"))
      (node (ref "C9") (pin "1") (pinfunction "1_1") (pintype "passive"))
      (node (ref "D2") (pin "2") (pinfunction "K_2") (pintype "passive"))
      (node (ref "D6") (pin "1") (pinfunction "A_1") (pintype "passive"))
      (node (ref "P14") (pin "1") (pinfunction "1_1") (pintype "passive"))
      (node (ref "P14") (pin "2") (pinfunction "2_2") (pintype "passive"))
      (node (ref "P14") (pin "3") (pinfunction "3_3") (pintype "passive"))
      (node (ref "P14") (pin "4") (pinfunction "4_4") (pintype "passive"))
      (node (ref "P14") (pin "5") (pinfunction "5_5") (pintype "passive"))
      (node (ref "P16") (pin "2") (pinfunction "2_2") (pintype "passive"))
      (node (ref "P3") (pin "1") (pinfunction "1_1") (pintype "passive"))
      (node (ref "P4") (pin "1") (pinfunction "1_1") (pintype "passive"))
      (node (ref "P7") (pin "4") (pinfunction "4_4") (pintype "passive"))
      (node (ref "P8") (pin "4") (pinfunction "4_4") (pintype "passive"))
      (node (ref "P9") (pin "4") (pinfunction "4_4") (pintype "passive"))
      (node (ref "R11") (pin "1") (pinfunction "1_1") (pintype "passive"))
      (node (ref "R2") (pin "1") (pinfunction "1_1") (pintype "passive"))
      (node (ref "R28") (pin "1") (pinfunction "1_1") (pintype "passive"))
      (node (ref "R5") (pin "1") (pinfunction "1_1") (pintype "passive"))
      (node (ref "U10") (pin "3") (pinfunction "VF-_3") (pintype "passive"))
      (node (ref "U11") (pin "3") (pinfunction "VF-_3") (pintype "passive"))
      (node (ref "U3") (pin "3") (pinfunction "GND_3") (pintype "passive"))
      (node (ref "U3") (pin "5") (pinfunction "EN_5") (pintype "passive"))
      (node (ref "U6") (pin "3") (pinfunction "VF-_3") (pintype "passive"))
      (node (ref "U7") (pin "3") (pinfunction "VF-_3") (pintype "passive"))
      (node (ref "U8") (pin "3") (pinfunction "VF-_3") (pintype "passive"))
      (node (ref "U9") (pin "3") (pinfunction "VF-_3") (pintype "passive"))
    )
    (net (code "124") (name "Motor1_GND") (class "Default")
      (node (ref "AR1") (pin "2") (pinfunction "IN+_2") (pintype "passive"))
      (node (ref "C7") (pin "2") (pinfunction "2_2") (pintype "passive"))
      (node (ref "R10") (pin "1") (pinfunction "1_1") (pintype "passive"))
      (node (ref "R2") (pin "2") (pinfunction "2_2") (pintype "passive"))
      (node (ref "R7") (pin "1") (pinfunction "1_1") (pintype "passive"))
      (node (ref "R8") (pin "1") (pinfunction "1_1") (pintype "passive"))
      (node (ref "R9") (pin "1") (pinfunction "1_1") (pintype "passive"))
      (node (ref "U1") (pin "1") (pinfunction "GND_1") (pintype "passive"))
      (node (ref "U10") (pin "5") (pinfunction "GND_5") (pintype "passive"))
      (node (ref "U2") (pin "1") (pinfunction "GND_1") (pintype "passive"))
      (node (ref "U7") (pin "5") (pinfunction "GND_5") (pintype "passive"))
      (node (ref "U8") (pin "5") (pinfunction "GND_5") (pintype "passive"))
    )
    (net (code "125") (name "Motor2_GND") (class "Default")
      (node (ref "AR2") (pin "2") (pinfunction "IN+_2") (pintype "passive"))
      (node (ref "C11") (pin "2") (pinfunction "2_2") (pintype "passive"))
      (node (ref "R16") (pin "1") (pinfunction "1_1") (pintype "passive"))
      (node (ref "R17") (pin "1") (pinfunction "1_1") (pintype "passive"))
      (node (ref "R18") (pin "1") (pinfunction "1_1") (pintype "passive"))
      (node (ref "R19") (pin "1") (pinfunction "1_1") (pintype "passive"))
      (node (ref "R5") (pin "2") (pinfunction "2_2") (pintype "passive"))
      (node (ref "U11") (pin "5") (pinfunction "GND_5") (pintype "passive"))
      (node (ref "U4") (pin "1") (pinfunction "GND_1") (pintype "passive"))
      (node (ref "U5") (pin "1") (pinfunction "GND_1") (pintype "passive"))
      (node (ref "U6") (pin "5") (pinfunction "GND_5") (pintype "passive"))
      (node (ref "U9") (pin "5") (pinfunction "GND_5") (pintype "passive"))
    )
    (net (code "126") (name "Net-(AR1-IN-)") (class "Default")
      (node (ref "AR1") (pin "1") (pinfunction "IN-_1") (pintype "passive"))
      (node (ref "R1") (pin "1") (pinfunction "1_1") (pintype "passive"))
      (node (ref "R28") (pin "2") (pinfunction "2_2") (pintype "passive"))
    )
    (net (code "127") (name "Net-(AR2-IN-)") (class "Default")
      (node (ref "AR2") (pin "1") (pinfunction "IN-_1") (pintype "passive"))
      (node (ref "R11") (pin "2") (pinfunction "2_2") (pintype "passive"))
      (node (ref "R4") (pin "1") (pinfunction "1_1") (pintype "passive"))
    )
    (net (code "128") (name "Net-(D2-A)") (class "Default")
      (node (ref "D2") (pin "1") (pinfunction "A_1") (pintype "passive"))
      (node (ref "R6") (pin "1") (pinfunction "1_1") (pintype "passive"))
    )
    (net (code "129") (name "Net-(D6-K)") (class "Default")
      (node (ref "D6") (pin "2") (pinfunction "K_2") (pintype "passive"))
      (node (ref "L1") (pin "1") (pinfunction "1_1") (pintype "passive"))
      (node (ref "U3") (pin "2") (pinfunction "OUT_2") (pintype "passive"))
    )
    (net (code "130") (name "Net-(P1-Pad1)") (class "Default")
      (node (ref "P1") (pin "1") (pinfunction "1_1") (pintype "passive"))
      (node (ref "R3") (pin "1") (pinfunction "1_1") (pintype "passive"))
    )
    (net (code "131") (name "Net-(P2-Pad1)") (class "Default")
      (node (ref "P2") (pin "1") (pinfunction "1_1") (pintype "passive"))
      (node (ref "R29") (pin "1") (pinfunction "1_1") (pintype "passive"))
    )
    (net (code "132") (name "Net-(U1-IS)") (class "Default")
      (node (ref "R8") (pin "2") (pinfunction "2_2") (pintype "passive"))
      (node (ref "U1") (pin "6") (pinfunction "IS_6") (pintype "passive"))
    )
    (net (code "133") (name "Net-(U1-SR)") (class "Default")
      (node (ref "R7") (pin "2") (pinfunction "2_2") (pintype "passive"))
      (node (ref "U1") (pin "5") (pinfunction "SR_5") (pintype "passive"))
    )
    (net (code "134") (name "Net-(U2-IS)") (class "Default")
      (node (ref "R10") (pin "2") (pinfunction "2_2") (pintype "passive"))
      (node (ref "U2") (pin "6") (pinfunction "IS_6") (pintype "passive"))
    )
    (net (code "135") (name "Net-(U2-SR)") (class "Default")
      (node (ref "R9") (pin "2") (pinfunction "2_2") (pintype "passive"))
      (node (ref "U2") (pin "5") (pinfunction "SR_5") (pintype "passive"))
    )
    (net (code "136") (name "Net-(U4-IS)") (class "Default")
      (node (ref "R17") (pin "2") (pinfunction "2_2") (pintype "passive"))
      (node (ref "U4") (pin "6") (pinfunction "IS_6") (pintype "passive"))
    )
    (net (code "137") (name "Net-(U4-SR)") (class "Default")
      (node (ref "R16") (pin "2") (pinfunction "2_2") (pintype "passive"))
      (node (ref "U4") (pin "5") (pinfunction "SR_5") (pintype "passive"))
    )
    (net (code "138") (name "Net-(U5-IS)") (class "Default")
      (node (ref "R19") (pin "2") (pinfunction "2_2") (pintype "passive"))
      (node (ref "U5") (pin "6") (pinfunction "IS_6") (pintype "passive"))
    )
    (net (code "139") (name "Net-(U5-SR)") (class "Default")
      (node (ref "R18") (pin "2") (pinfunction "2_2") (pintype "passive"))
      (node (ref "U5") (pin "5") (pinfunction "SR_5") (pintype "passive"))
    )
    (net (code "140") (name "Net-(U6-VF+)") (class "Default")
      (node (ref "R14") (pin "1") (pinfunction "1_1") (pintype "passive"))
      (node (ref "U6") (pin "2") (pinfunction "VF+_2") (pintype "passive"))
    )
    (net (code "141") (name "Net-(U7-VF+)") (class "Default")
      (node (ref "R15") (pin "1") (pinfunction "1_1") (pintype "passive"))
      (node (ref "U7") (pin "2") (pinfunction "VF+_2") (pintype "passive"))
    )
    (net (code "142") (name "Net-(U8-VF+)") (class "Default")
      (node (ref "R22") (pin "1") (pinfunction "1_1") (pintype "passive"))
      (node (ref "U8") (pin "2") (pinfunction "VF+_2") (pintype "passive"))
    )
    (net (code "143") (name "Net-(U9-VF+)") (class "Default")
      (node (ref "R23") (pin "1") (pinfunction "1_1") (pintype "passive"))
      (node (ref "U9") (pin "2") (pinfunction "VF+_2") (pintype "passive"))
    )
    (net (code "144") (name "Net-(U10-VF+)") (class "Default")
      (node (ref "R26") (pin "1") (pinfunction "1_1") (pintype "passive"))
      (node (ref "U10") (pin "2") (pinfunction "VF+_2") (pintype "passive"))
    )
    (net (code "145") (name "Net-(U11-VF+)") (class "Default")
      (node (ref "R27") (pin "1") (pinfunction "1_1") (pintype "passive"))
      (node (ref "U11") (pin "2") (pinfunction "VF+_2") (pintype "passive"))
    )
    (net (code "146") (name "VCC-5") (class "Default")
      (node (ref "AR1") (pin "4") (pinfunction "V+_4") (pintype "passive"))
      (node (ref "AR2") (pin "4") (pinfunction "V+_4") (pintype "passive"))
      (node (ref "C2") (pin "1") (pinfunction "+_1") (pintype "passive"))
      (node (ref "C3") (pin "1") (pinfunction "1_1") (pintype "passive"))
      (node (ref "C4") (pin "2") (pinfunction "2_2") (pintype "passive"))
      (node (ref "C5") (pin "1") (pinfunction "1_1") (pintype "passive"))
      (node (ref "C8") (pin "1") (pinfunction "1_1") (pintype "passive"))
      (node (ref "C9") (pin "2") (pinfunction "2_2") (pintype "passive"))
      (node (ref "L1") (pin "2") (pinfunction "2_2") (pintype "passive"))
      (node (ref "P15") (pin "1") (pinfunction "1_1") (pintype "passive"))
      (node (ref "P15") (pin "2") (pinfunction "2_2") (pintype "passive"))
      (node (ref "P15") (pin "3") (pinfunction "3_3") (pintype "passive"))
      (node (ref "P15") (pin "4") (pinfunction "4_4") (pintype "passive"))
      (node (ref "P15") (pin "5") (pinfunction "5_5") (pintype "passive"))
      (node (ref "P3") (pin "2") (pinfunction "2_2") (pintype "passive"))
      (node (ref "P4") (pin "2") (pinfunction "2_2") (pintype "passive"))
      (node (ref "P7") (pin "3") (pinfunction "3_3") (pintype "passive"))
      (node (ref "P8") (pin "3") (pinfunction "3_3") (pintype "passive"))
      (node (ref "P9") (pin "3") (pinfunction "3_3") (pintype "passive"))
      (node (ref "R12") (pin "2") (pinfunction "2_2") (pintype "passive"))
      (node (ref "R13") (pin "2") (pinfunction "2_2") (pintype "passive"))
      (node (ref "R20") (pin "2") (pinfunction "2_2") (pintype "passive"))
      (node (ref "R21") (pin "2") (pinfunction "2_2") (pintype "passive"))
      (node (ref "R24") (pin "2") (pinfunction "2_2") (pintype "passive"))
      (node (ref "R25") (pin "2") (pinfunction "2_2") (pintype "passive"))
      (node (ref "R6") (pin "2") (pinfunction "2_2") (pintype "passive"))
      (node (ref "U10") (pin "7") (pinfunction "VE_7") (pintype "passive"))
      (node (ref "U10") (pin "8") (pinfunction "VCC_8") (pintype "passive"))
      (node (ref "U11") (pin "7") (pinfunction "VE_7") (pintype "passive"))
      (node (ref "U11") (pin "8") (pinfunction "VCC_8") (pintype "passive"))
      (node (ref "U3") (pin "4") (pinfunction "F_4") (pintype "passive"))
      (node (ref "U6") (pin "7") (pinfunction "VE_7") (pintype "passive"))
      (node (ref "U6") (pin "8") (pinfunction "VCC_8") (pintype "passive"))
      (node (ref "U7") (pin "7") (pinfunction "VE_7") (pintype "passive"))
      (node (ref "U7") (pin "8") (pinfunction "VCC_8") (pintype "passive"))
      (node (ref "U8") (pin "7") (pinfunction "VE_7") (pintype "passive"))
      (node (ref "U8") (pin "8") (pinfunction "VCC_8") (pintype "passive"))
      (node (ref "U9") (pin "7") (pinfunction "VE_7") (pintype "passive"))
      (node (ref "U9") (pin "8") (pinfunction "VCC_8") (pintype "passive"))
    )
    (net (code "147") (name "VCC-12") (class "Default")
      (node (ref "C1") (pin "1") (pinfunction "+_1") (pintype "passive"))
      (node (ref "P16") (pin "1") (pinfunction "1_1") (pintype "passive"))
      (node (ref "U1") (pin "7") (pinfunction "VS_7") (pintype "passive"))
      (node (ref "U2") (pin "7") (pinfunction "VS_7") (pintype "passive"))
      (node (ref "U3") (pin "1") (pinfunction "VIN_1") (pintype "passive"))
      (node (ref "U4") (pin "7") (pinfunction "VS_7") (pintype "passive"))
      (node (ref "U5") (pin "7") (pinfunction "VS_7") (pintype "passive"))
    )
    (net (code "148") (name "unconnected-(U1-OUT-Pad8)") (class "Default")
      (node (ref "U1") (pin "8") (pinfunction "OUT_8") (pintype "output"))
    )
    (net (code "149") (name "unconnected-(U2-OUT-Pad8)") (class "Default")
      (node (ref "U2") (pin "8") (pinfunction "OUT_8") (pintype "output"))
    )
    (net (code "150") (name "unconnected-(U4-OUT-Pad8)") (class "Default")
      (node (ref "U4") (pin "8") (pinfunction "OUT_8") (pintype "output"))
    )
    (net (code "151") (name "unconnected-(U5-OUT-Pad8)") (class "Default")
      (node (ref "U5") (pin "8") (pinfunction "OUT_8") (pintype "output"))
    )
    (net (code "152") (name "unconnected-(U6-NC-Pad1)") (class "Default")
      (node (ref "U6") (pin "1") (pinfunction "NC_1") (pintype "passive"))
    )
    (net (code "153") (name "unconnected-(U6-NC-Pad4)") (class "Default")
      (node (ref "U6") (pin "4") (pinfunction "NC_4") (pintype "passive"))
    )
    (net (code "154") (name "unconnected-(U7-NC-Pad1)") (class "Default")
      (node (ref "U7") (pin "1") (pinfunction "NC_1") (pintype "passive"))
    )
    (net (code "155") (name "unconnected-(U7-NC-Pad4)") (class "Default")
      (node (ref "U7") (pin "4") (pinfunction "NC_4") (pintype "passive"))
    )
    (net (code "156") (name "unconnected-(U8-NC-Pad1)") (class "Default")
      (node (ref "U8") (pin "1") (pinfunction "NC_1") (pintype "passive"))
    )
    (net (code "157") (name "unconnected-(U8-NC-Pad4)") (class "Default")
      (node (ref "U8") (pin "4") (pinfunction "NC_4") (pintype "passive"))
    )
    (net (code "158") (name "unconnected-(U9-NC-Pad1)") (class "Default")
      (node (ref "U9") (pin "1") (pinfunction "NC_1") (pintype "passive"))
    )
    (net (code "159") (name "unconnected-(U9-NC-Pad4)") (class "Default")
      (node (ref "U9") (pin "4") (pinfunction "NC_4") (pintype "passive"))
    )
    (net (code "160") (name "unconnected-(U10-NC-Pad1)") (class "Default")
      (node (ref "U10") (pin "1") (pinfunction "NC_1") (pintype "passive"))
    )
    (net (code "161") (name "unconnected-(U10-NC-Pad4)") (class "Default")
      (node (ref "U10") (pin "4") (pinfunction "NC_4") (pintype "passive"))
    )
    (net (code "162") (name "unconnected-(U11-NC-Pad1)") (class "Default")
      (node (ref "U11") (pin "1") (pinfunction "NC_1") (pintype "passive"))
    )
    (net (code "163") (name "unconnected-(U11-NC-Pad4)") (class "Default")
      (node (ref "U11") (pin "4") (pinfunction "NC_4") (pintype "passive"))
    )
  )
)
